# Sheet2.net
KiCad netlist of a schematic drawn in Altium Designer
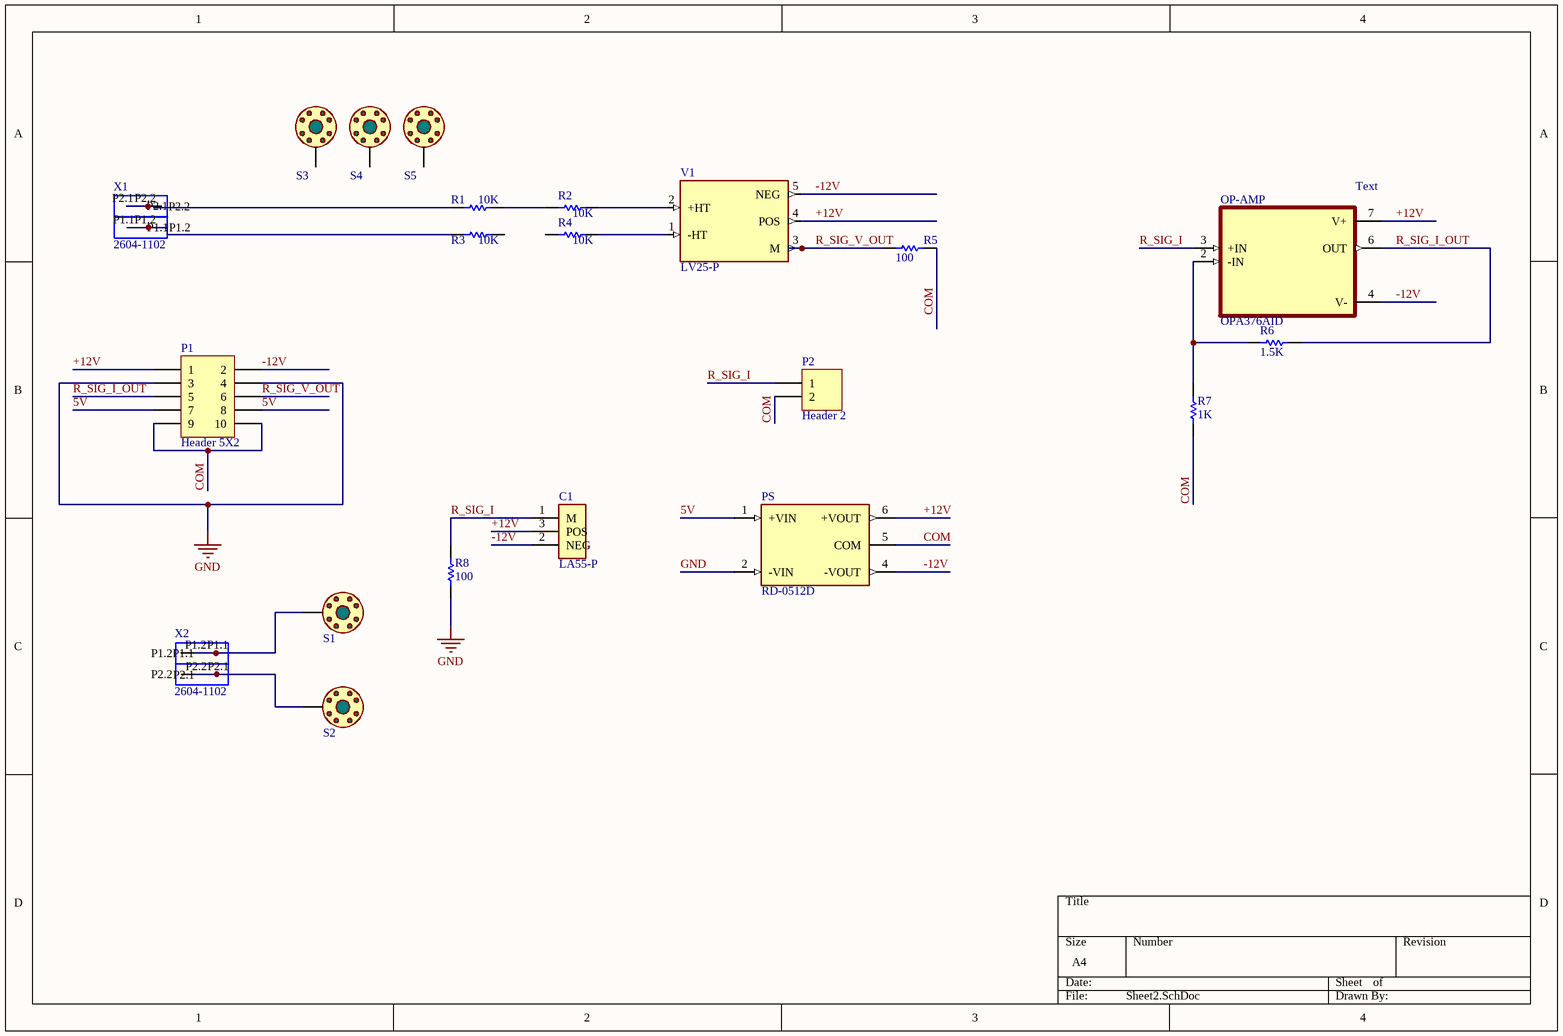
[diagram p0: Sheet2.SchDoc]

(export (version "E")
  (design (tool "Eeschema 10.0.6"))
  (components
    (comp (ref "C1")
      (value "LA55-P")
      (footprint "XDCR_LA55-P")
      (description "Current Sensor 50A 1 Channel Hall Effect, Closed Loop Bidirectional Module, Single Pass Through")
      (fields (field (name "MF") "LEM USA") (field (name "MP") "LA 55-P"))
      (libsource (lib "altium-import") (part "root_0_LA55-P_"))
    )
    (comp (ref "OP-AMP")
      (value "OPA376AID")
      (footprint "SOIC127P599X175-8N")
      (fields
        (field (name "MF") "Texas Instruments")
        (field (name "BUYPART") "https://www.snapeda.com/parts/OPA376AID/Texas%20Instruments/view-part/572715/?ref=eda")
      )
      (libsource (lib "altium-import") (part "root_0_OPA376AID_"))
    )
    (comp (ref "P1")
      (value "Header 5X2")
      (footprint "HDR2X5")
      (description "Header, 5-Pin, Dual row")
      (fields (field (name "PUBLISHER") "Altium Limited"))
      (libsource (lib "Miscellaneous Connectors") (part "Header 5X2"))
    )
    (comp (ref "P2")
      (value "Header 2")
      (footprint "HDR1X2")
      (description "Header, 2-Pin")
      (fields (field (name "PUBLISHER") "Altium Limited"))
      (libsource (lib "Miscellaneous Connectors") (part "Header 2"))
    )
    (comp (ref "PS")
      (value "RD-0512D")
      (footprint "CONV_RD-0512D")
      (description "2W DC/DC-Converter 'ECONOLINE' SIP7 1kV unreg")
      (fields (field (name "DIGI-KEY_PART_NUMBER") "945-1821-5-ND") (field (name "MF") "Recom Power"))
      (libsource (lib "altium-import") (part "root_0_RD-0512D_"))
    )
    (comp (ref "R1")
      (value "10K")
      (footprint "MY_(3w)_0817V")
      (description "Standard resistor")
      (fields (field (name "ASID PART NUMBER") "Res-AS"))
      (libsource (lib "altium-import") (part "root_3_Res_"))
    )
    (comp (ref "R2")
      (value "10K")
      (footprint "MY_(3w)_0817V")
      (description "Standard resistor")
      (fields (field (name "ASID PART NUMBER") "Res-AS"))
      (libsource (lib "altium-import") (part "root_1_Res_"))
    )
    (comp (ref "R3")
      (value "10K")
      (footprint "MY_(3w)_0817V")
      (description "Standard resistor")
      (fields (field (name "ASID PART NUMBER") "Res-AS"))
      (libsource (lib "altium-import") (part "root_1_Res_"))
    )
    (comp (ref "R4")
      (value "10K")
      (footprint "MY_(3w)_0817V")
      (description "Standard resistor")
      (fields (field (name "ASID PART NUMBER") "Res-AS"))
      (libsource (lib "altium-import") (part "root_1_Res_"))
    )
    (comp (ref "R5")
      (value "100")
      (footprint "MY_0805")
      (description "Standard resistor")
      (fields (field (name "ASID PART NUMBER") "Res-AS"))
      (libsource (lib "altium-import") (part "root_1_Res_"))
    )
    (comp (ref "R6")
      (value "1.5K")
      (footprint "MY_1206")
      (description "Standard resistor")
      (fields (field (name "ASID PART NUMBER") "Res-AS"))
      (libsource (lib "altium-import") (part "root_1_Res_"))
    )
    (comp (ref "R7")
      (value "1K")
      (footprint "MY_1206")
      (description "Standard resistor")
      (fields (field (name "ASID PART NUMBER") "Res-AS"))
      (libsource (lib "altium-import") (part "root_0_Res_"))
    )
    (comp (ref "R8")
      (value "100")
      (footprint "MY_0805")
      (description "Standard resistor")
      (fields (field (name "ASID PART NUMBER") "Res-AS"))
      (libsource (lib "PCB_Project1") (part "Res"))
    )
    (comp (ref "S1")
      (value "Screw")
      (footprint "MY_PAD_3MM")
      (description "3mm Screw")
      (fields (field (name "ASID PART NUMBER") "Screw-AS"))
      (libsource (lib "altium-import") (part "root_0_Screw_"))
    )
    (comp (ref "S2")
      (value "Screw")
      (footprint "MY_PAD_3MM")
      (description "3mm Screw")
      (fields (field (name "ASID PART NUMBER") "Screw-AS"))
      (libsource (lib "altium-import") (part "root_0_Screw_"))
    )
    (comp (ref "S3")
      (value "Screw")
      (footprint "MY_PAD_3MM")
      (description "3mm Screw")
      (fields (field (name "ASID PART NUMBER") "Screw-AS"))
      (libsource (lib "altium-import") (part "root_1_Screw_"))
    )
    (comp (ref "S4")
      (value "Screw")
      (footprint "MY_PAD_3MM")
      (description "3mm Screw")
      (fields (field (name "ASID PART NUMBER") "Screw-AS"))
      (libsource (lib "altium-import") (part "root_1_Screw_"))
    )
    (comp (ref "S5")
      (value "Screw")
      (footprint "MY_PAD_3MM")
      (description "3mm Screw")
      (fields (field (name "ASID PART NUMBER") "Screw-AS"))
      (libsource (lib "altium-import") (part "root_1_Screw_"))
    )
    (comp (ref "V1")
      (value "LV25-P")
      (footprint "XDCR_LV25-P")
      (description "Voltage, Closed Loop Sensor Voltage Output")
      (fields (field (name "DIGI-KEY_PART_NUMBER") "398-1019-ND") (field (name "MF") "LEM USA Inc."))
      (libsource (lib "altium-import") (part "root_0_LV25-P_"))
    )
    (comp (ref "X1")
      (value "2604-1102")
      (footprint "P-2604-1102")
      (description "2 Position Wire to Board Terminal Block Horizontal with Board 0.197 (5.00mm) Through Hole")
      (fields (field (name "MF") "WAGO Innovative Connections"))
      (libsource (lib "altium-import") (part "root_2_2604-1102_"))
    )
    (comp (ref "X2")
      (value "2604-1102")
      (footprint "P-2604-1102")
      (description "2 Position Wire to Board Terminal Block Horizontal with Board 0.197 (5.00mm) Through Hole")
      (fields (field (name "MF") "WAGO Innovative Connections"))
      (libsource (lib "altium-import") (part "root_0_2604-1102_"))
    )
  )
  (nets
    (net (code "1") (name "/+12V") (class "Default")
      (node (ref "C1") (pin "3") (pinfunction "POS_3") (pintype "power_in"))
      (node (ref "OP-AMP") (pin "7") (pinfunction "V+_7") (pintype "power_in"))
      (node (ref "P1") (pin "1") (pinfunction "1_1") (pintype "passive"))
      (node (ref "PS") (pin "6") (pinfunction "+VOUT_6") (pintype "output"))
      (node (ref "V1") (pin "4") (pinfunction "POS_4") (pintype "output"))
    )
    (net (code "2") (name "/-12V") (class "Default")
      (node (ref "C1") (pin "2") (pinfunction "NEG_2") (pintype "power_in"))
      (node (ref "OP-AMP") (pin "4") (pinfunction "V-_4") (pintype "power_in"))
      (node (ref "P1") (pin "2") (pinfunction "2_2") (pintype "passive"))
      (node (ref "PS") (pin "4") (pinfunction "-VOUT_4") (pintype "output"))
      (node (ref "V1") (pin "5") (pinfunction "NEG_5") (pintype "output"))
    )
    (net (code "3") (name "/5V") (class "Default")
      (node (ref "P1") (pin "7") (pinfunction "7_7") (pintype "passive"))
      (node (ref "P1") (pin "8") (pinfunction "8_8") (pintype "passive"))
      (node (ref "PS") (pin "1") (pinfunction "+VIN_1") (pintype "input"))
    )
    (net (code "4") (name "/COM") (class "Default")
      (node (ref "P1") (pin "10") (pinfunction "10_10") (pintype "passive"))
      (node (ref "P1") (pin "9") (pinfunction "9_9") (pintype "passive"))
      (node (ref "P2") (pin "2") (pinfunction "2_2") (pintype "passive"))
      (node (ref "PS") (pin "5") (pinfunction "COM_5") (pintype "power_in"))
      (node (ref "R5") (pin "2") (pinfunction "2_2") (pintype "passive"))
      (node (ref "R7") (pin "2") (pinfunction "2_2") (pintype "passive"))
    )
    (net (code "5") (name "/R_SIG_I") (class "Default")
      (node (ref "C1") (pin "1") (pinfunction "M_1") (pintype "power_in"))
      (node (ref "OP-AMP") (pin "3") (pinfunction "+IN_3") (pintype "input"))
      (node (ref "P2") (pin "1") (pinfunction "1_1") (pintype "passive"))
      (node (ref "R8") (pin "1") (pinfunction "1_1") (pintype "passive"))
    )
    (net (code "6") (name "/R_SIG_I_OUT") (class "Default")
      (node (ref "OP-AMP") (pin "6") (pinfunction "OUT_6") (pintype "output"))
      (node (ref "P1") (pin "5") (pinfunction "5_5") (pintype "passive"))
      (node (ref "R6") (pin "2") (pinfunction "2_2") (pintype "passive"))
    )
    (net (code "7") (name "/R_SIG_V_OUT") (class "Default")
      (node (ref "P1") (pin "6") (pinfunction "6_6") (pintype "passive"))
      (node (ref "R5") (pin "1") (pinfunction "1_1") (pintype "passive"))
      (node (ref "V1") (pin "3") (pinfunction "M_3") (pintype "output"))
    )
    (net (code "8") (name "GND") (class "Default")
      (node (ref "P1") (pin "3") (pinfunction "3_3") (pintype "passive"))
      (node (ref "P1") (pin "4") (pinfunction "4_4") (pintype "passive"))
      (node (ref "PS") (pin "2") (pinfunction "-VIN_2") (pintype "input"))
      (node (ref "R8") (pin "2") (pinfunction "2_2") (pintype "passive"))
    )
    (net (code "9") (name "Net-(OP-AMP--IN)") (class "Default")
      (node (ref "OP-AMP") (pin "2") (pinfunction "-IN_2") (pintype "input"))
      (node (ref "R6") (pin "1") (pinfunction "1_1") (pintype "passive"))
      (node (ref "R7") (pin "1") (pinfunction "1_1") (pintype "passive"))
    )
    (net (code "10") (name "Net-(R1-Pad1)") (class "Default")
      (node (ref "R1") (pin "1") (pinfunction "1_1") (pintype "passive"))
      (node (ref "R2") (pin "1") (pinfunction "1_1") (pintype "passive"))
    )
    (net (code "11") (name "Net-(R1-Pad2)") (class "Default")
      (node (ref "R1") (pin "2") (pinfunction "2_2") (pintype "passive"))
      (node (ref "X1") (pin "P2.1") (pinfunction "P2.1_P2.1") (pintype "bidirectional"))
      (node (ref "X1") (pin "P2.2") (pinfunction "P2.2_P2.2") (pintype "bidirectional"))
    )
    (net (code "12") (name "Net-(R3-Pad1)") (class "Default")
      (node (ref "R3") (pin "1") (pinfunction "1_1") (pintype "passive"))
      (node (ref "X1") (pin "P1.1") (pinfunction "P1.1_P1.1") (pintype "bidirectional"))
      (node (ref "X1") (pin "P1.2") (pinfunction "P1.2_P1.2") (pintype "bidirectional"))
    )
    (net (code "13") (name "Net-(S1-Pad0)") (class "Default")
      (node (ref "S1") (pin "0") (pinfunction "0_0") (pintype "passive"))
      (node (ref "X2") (pin "P1.1") (pinfunction "P1.1_P1.1") (pintype "bidirectional"))
      (node (ref "X2") (pin "P1.2") (pinfunction "P1.2_P1.2") (pintype "bidirectional"))
    )
    (net (code "14") (name "Net-(S2-Pad0)") (class "Default")
      (node (ref "S2") (pin "0") (pinfunction "0_0") (pintype "passive"))
      (node (ref "X2") (pin "P2.1") (pinfunction "P2.1_P2.1") (pintype "bidirectional"))
      (node (ref "X2") (pin "P2.2") (pinfunction "P2.2_P2.2") (pintype "bidirectional"))
    )
    (net (code "15") (name "Net-(V1-+HT)") (class "Default")
      (node (ref "R2") (pin "2") (pinfunction "2_2") (pintype "passive"))
      (node (ref "V1") (pin "2") (pinfunction "+HT_2") (pintype "input"))
    )
    (net (code "16") (name "Net-(V1--HT)") (class "Default")
      (node (ref "R4") (pin "2") (pinfunction "2_2") (pintype "passive"))
      (node (ref "V1") (pin "1") (pinfunction "-HT_1") (pintype "input"))
    )
    (net (code "17") (name "unconnected-(R3-Pad2)") (class "Default")
      (node (ref "R3") (pin "2") (pinfunction "2_2") (pintype "passive"))
    )
    (net (code "18") (name "unconnected-(R4-Pad1)") (class "Default")
      (node (ref "R4") (pin "1") (pinfunction "1_1") (pintype "passive"))
    )
    (net (code "19") (name "unconnected-(S3-Pad0)") (class "Default")
      (node (ref "S3") (pin "0") (pinfunction "0_0") (pintype "passive"))
    )
    (net (code "20") (name "unconnected-(S4-Pad0)") (class "Default")
      (node (ref "S4") (pin "0") (pinfunction "0_0") (pintype "passive"))
    )
    (net (code "21") (name "unconnected-(S5-Pad0)") (class "Default")
      (node (ref "S5") (pin "0") (pinfunction "0_0") (pintype "passive"))
    )
  )
)
